# ESPROG.net
KiCad netlist of a schematic drawn in EAGLE
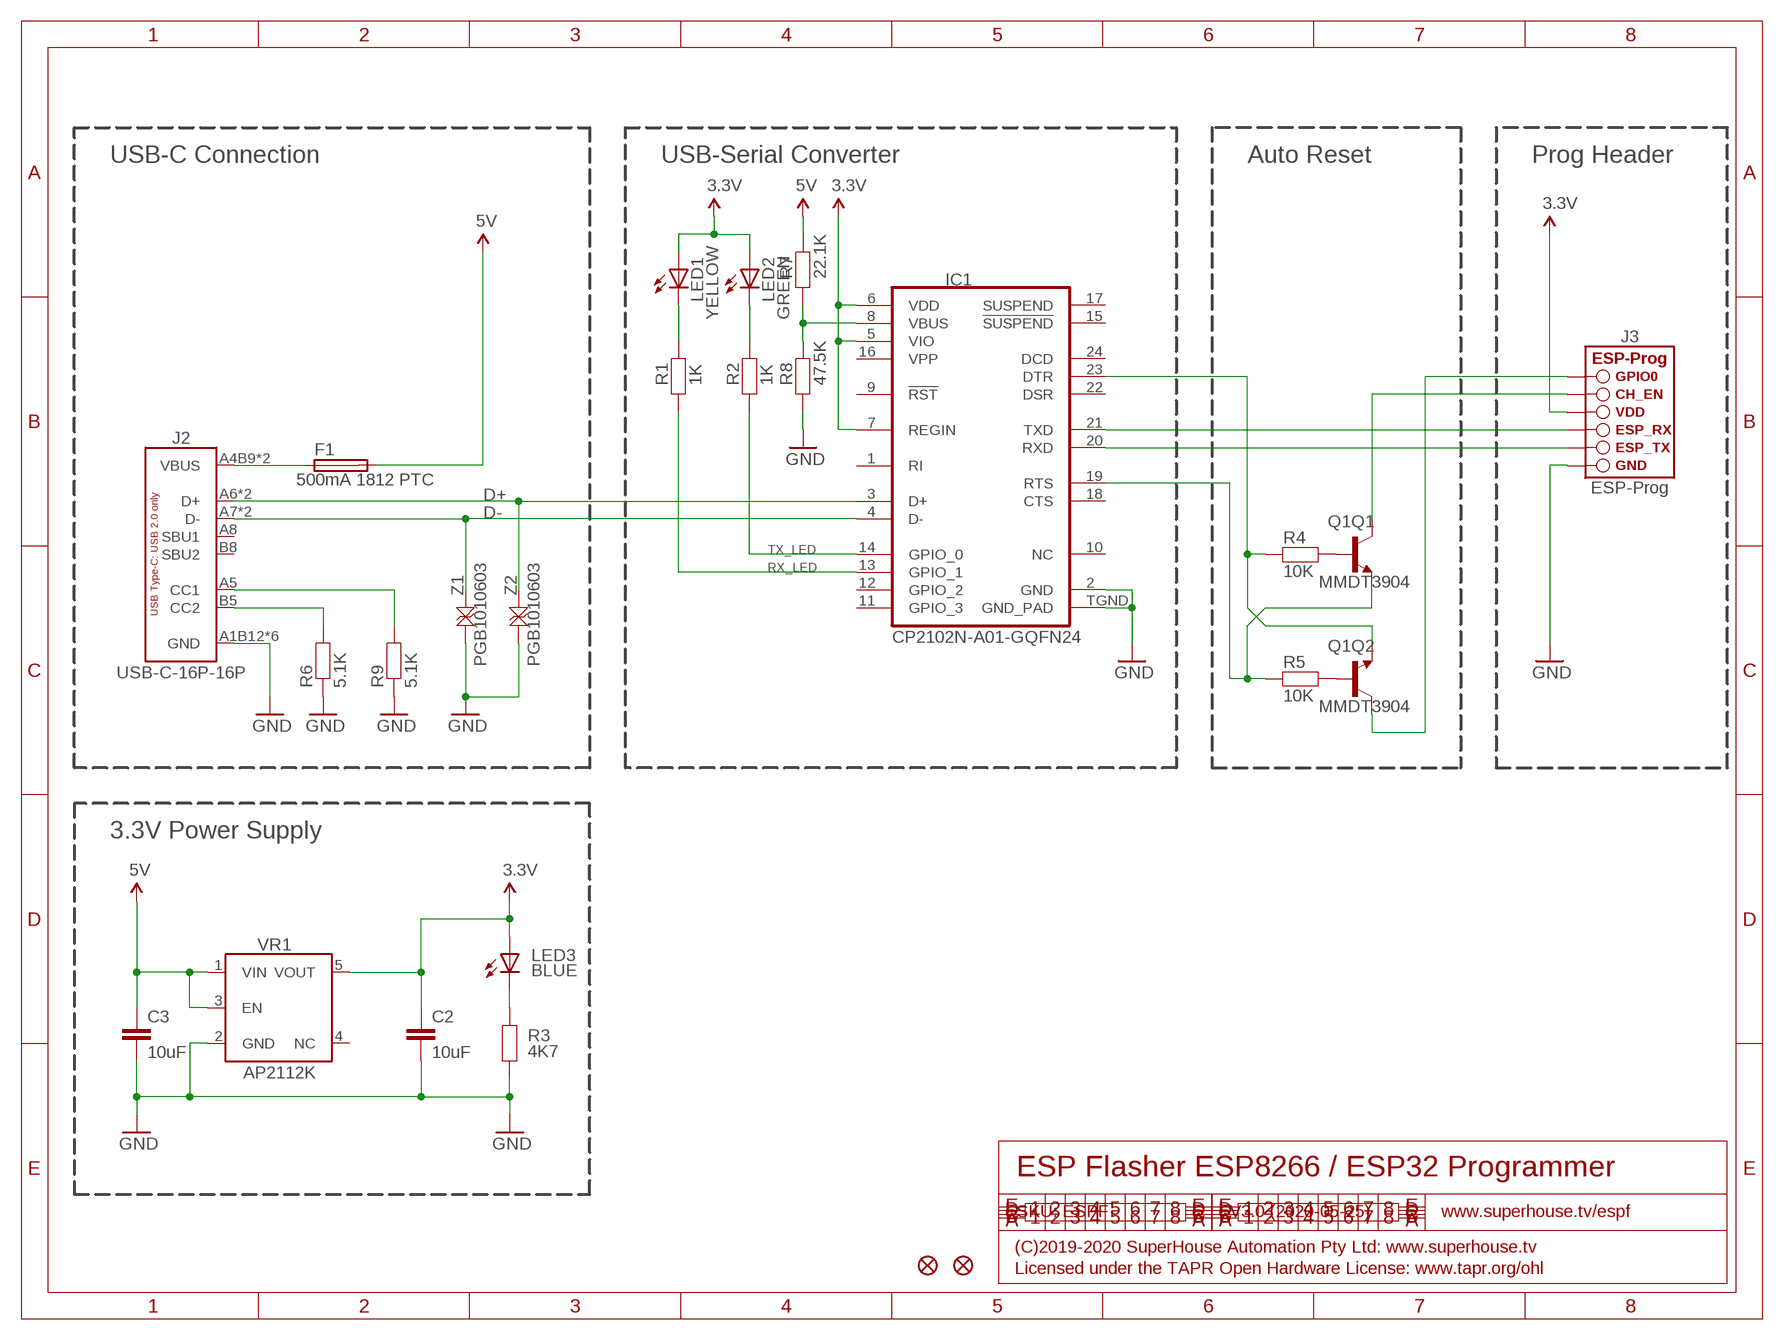
[diagram p0: schematic, sheet 1]

(export (version "E")
  (design (tool "Eeschema 10.0.6"))
  (components
    (comp (ref "C2")
      (value "10uF")
      (footprint "eagle-import:C0805")
      (libsource (lib "eagle-import") (part "CAP0805"))
    )
    (comp (ref "C3")
      (value "10uF")
      (footprint "eagle-import:C0805")
      (libsource (lib "eagle-import") (part "CAP0805"))
    )
    (comp (ref "F1")
      (value "500mA 1812 PTC")
      (footprint "eagle-import:1812")
      (libsource (lib "eagle-import") (part "PTC050"))
    )
    (comp (ref "FID1")
      (value "FIDUCIAL1X2.5")
      (footprint "eagle-import:FIDUCIAL-1X2.5")
      (libsource (lib "eagle-import") (part "FIDUCIAL1X2.5"))
    )
    (comp (ref "FID2")
      (value "FIDUCIAL1X2.5")
      (footprint "eagle-import:FIDUCIAL-1X2.5")
      (libsource (lib "eagle-import") (part "FIDUCIAL1X2.5"))
    )
    (comp (ref "IC1")
      (value "CP2102N-A01-GQFN24")
      (footprint "eagle-import:QFN-24")
      (libsource (lib "eagle-import") (part "CP2104"))
    )
    (comp (ref "J2")
      (value "USB-C-16P-16P")
      (footprint "eagle-import:USB-C-16P")
      (libsource (lib "eagle-import") (part "USB-C-16P-16P"))
    )
    (comp (ref "J3")
      (value "ESP-PROG-1X6-2.54-PINS-RA")
      (footprint "eagle-import:1X6-2.54-PINS-RA")
      (libsource (lib "eagle-import") (part "ESP-PROG-1X6-2.54-PINS-RA"))
    )
    (comp (ref "LED1")
      (value "YELLOW")
      (footprint "eagle-import:LED-0603")
      (libsource (lib "eagle-import") (part "LED0603"))
    )
    (comp (ref "LED2")
      (value "GREEN")
      (footprint "eagle-import:LED-0603")
      (libsource (lib "eagle-import") (part "LED0603"))
    )
    (comp (ref "LED3")
      (value "BLUE")
      (footprint "eagle-import:LED-0603")
      (libsource (lib "eagle-import") (part "LED0603"))
    )
    (comp (ref "Q1")
      (value "MMDT3904")
      (footprint "eagle-import:SOT-363")
      (libsource (lib "eagle-import") (part "TRANS_NPN_DUAL-MMDT3904"))
    )
    (comp (ref "R1")
      (value "1K")
      (footprint "eagle-import:R0603")
      (libsource (lib "eagle-import") (part "RESISTOR0603"))
    )
    (comp (ref "R2")
      (value "1K")
      (footprint "eagle-import:R0603")
      (libsource (lib "eagle-import") (part "RESISTOR0603"))
    )
    (comp (ref "R3")
      (value "4K7")
      (footprint "eagle-import:R0603")
      (libsource (lib "eagle-import") (part "RESISTOR0603"))
    )
    (comp (ref "R4")
      (value "10K")
      (footprint "eagle-import:R0603")
      (libsource (lib "eagle-import") (part "RESISTOR0603"))
    )
    (comp (ref "R5")
      (value "10K")
      (footprint "eagle-import:R0603")
      (libsource (lib "eagle-import") (part "RESISTOR0603"))
    )
    (comp (ref "R6")
      (value "5.1K")
      (footprint "eagle-import:R0603")
      (libsource (lib "eagle-import") (part "RESISTOR0603"))
    )
    (comp (ref "R7")
      (value "22.1K")
      (footprint "eagle-import:R0603")
      (libsource (lib "eagle-import") (part "RESISTOR0603"))
    )
    (comp (ref "R8")
      (value "47.5K")
      (footprint "eagle-import:R0603")
      (libsource (lib "eagle-import") (part "RESISTOR0603"))
    )
    (comp (ref "R9")
      (value "5.1K")
      (footprint "eagle-import:R0603")
      (libsource (lib "eagle-import") (part "RESISTOR0603"))
    )
    (comp (ref "VR1")
      (value "AP2112KSOT25")
      (footprint "eagle-import:SOT23-5")
      (libsource (lib "eagle-import") (part "AP2112KSOT25"))
    )
    (comp (ref "Z1")
      (value "PGB1010603")
      (footprint "eagle-import:TVS0603")
      (libsource (lib "eagle-import") (part "TVS0603"))
    )
    (comp (ref "Z2")
      (value "PGB1010603")
      (footprint "eagle-import:TVS0603")
      (libsource (lib "eagle-import") (part "TVS0603"))
    )
  )
  (nets
    (net (code "1") (name "/D+") (class "Default")
      (node (ref "IC1") (pin "3") (pinfunction "D+_3") (pintype "bidirectional"))
      (node (ref "J2") (pin "A6") (pinfunction "D+_A6") (pintype "bidirectional"))
      (node (ref "J2") (pin "B6") (pinfunction "D+_B6") (pintype "bidirectional"))
      (node (ref "Z2") (pin "2") (pinfunction "2_2") (pintype "passive"))
    )
    (net (code "2") (name "/D-") (class "Default")
      (node (ref "IC1") (pin "4") (pinfunction "D-_4") (pintype "bidirectional"))
      (node (ref "J2") (pin "A7") (pinfunction "D-_A7") (pintype "bidirectional"))
      (node (ref "J2") (pin "B7") (pinfunction "D-_B7") (pintype "bidirectional"))
      (node (ref "Z1") (pin "2") (pinfunction "2_2") (pintype "passive"))
    )
    (net (code "3") (name "/RX_LED") (class "Default")
      (node (ref "IC1") (pin "13") (pinfunction "GPIO_1_13") (pintype "bidirectional"))
      (node (ref "R1") (pin "1") (pinfunction "1_1") (pintype "passive"))
    )
    (net (code "4") (name "/TX_LED") (class "Default")
      (node (ref "IC1") (pin "14") (pinfunction "GPIO_0_14") (pintype "bidirectional"))
      (node (ref "R2") (pin "1") (pinfunction "1_1") (pintype "passive"))
    )
    (net (code "5") (name "3.3V") (class "Default")
      (node (ref "C2") (pin "1") (pinfunction "1_1") (pintype "passive"))
      (node (ref "IC1") (pin "5") (pinfunction "VIO_5") (pintype "bidirectional"))
      (node (ref "IC1") (pin "6") (pinfunction "VDD_6") (pintype "power_in"))
      (node (ref "IC1") (pin "7") (pinfunction "REGIN_7") (pintype "power_in"))
      (node (ref "J3") (pin "4") (pinfunction "VDD_4") (pintype "passive"))
      (node (ref "LED1") (pin "A") (pinfunction "A_A") (pintype "passive"))
      (node (ref "LED2") (pin "A") (pinfunction "A_A") (pintype "passive"))
      (node (ref "LED3") (pin "A") (pinfunction "A_A") (pintype "passive"))
      (node (ref "VR1") (pin "5") (pinfunction "VOUT_5") (pintype "bidirectional"))
    )
    (net (code "6") (name "5V") (class "Default")
      (node (ref "C3") (pin "1") (pinfunction "1_1") (pintype "passive"))
      (node (ref "F1") (pin "2") (pinfunction "2_2") (pintype "passive"))
      (node (ref "R7") (pin "2") (pinfunction "2_2") (pintype "passive"))
      (node (ref "VR1") (pin "1") (pinfunction "VIN_1") (pintype "bidirectional"))
      (node (ref "VR1") (pin "3") (pinfunction "EN_3") (pintype "bidirectional"))
    )
    (net (code "7") (name "GND") (class "Default")
      (node (ref "C2") (pin "2") (pinfunction "2_2") (pintype "passive"))
      (node (ref "C3") (pin "2") (pinfunction "2_2") (pintype "passive"))
      (node (ref "IC1") (pin "2") (pinfunction "GND_2") (pintype "power_in"))
      (node (ref "IC1") (pin "TGND") (pinfunction "GND_PAD_TGND") (pintype "power_in"))
      (node (ref "J2") (pin "A12B1") (pinfunction "GND_A12B1") (pintype "power_in"))
      (node (ref "J2") (pin "A1B12") (pinfunction "GND_A1B12") (pintype "power_in"))
      (node (ref "J2") (pin "FIX1") (pinfunction "GND_FIX1") (pintype "power_in"))
      (node (ref "J2") (pin "FIX2") (pinfunction "GND_FIX2") (pintype "power_in"))
      (node (ref "J2") (pin "FIX3") (pinfunction "GND_FIX3") (pintype "power_in"))
      (node (ref "J2") (pin "FIX4") (pinfunction "GND_FIX4") (pintype "power_in"))
      (node (ref "J3") (pin "1") (pinfunction "GND_1") (pintype "passive"))
      (node (ref "R3") (pin "1") (pinfunction "1_1") (pintype "passive"))
      (node (ref "R6") (pin "1") (pinfunction "1_1") (pintype "passive"))
      (node (ref "R8") (pin "1") (pinfunction "1_1") (pintype "passive"))
      (node (ref "R9") (pin "1") (pinfunction "1_1") (pintype "passive"))
      (node (ref "VR1") (pin "2") (pinfunction "GND_2") (pintype "bidirectional"))
      (node (ref "Z1") (pin "1") (pinfunction "1_1") (pintype "passive"))
      (node (ref "Z2") (pin "1") (pinfunction "1_1") (pintype "passive"))
    )
    (net (code "8") (name "Net-(F1-Pad1)") (class "Default")
      (node (ref "F1") (pin "1") (pinfunction "1_1") (pintype "passive"))
      (node (ref "J2") (pin "A4B9") (pinfunction "VBUS_A4B9") (pintype "power_in"))
      (node (ref "J2") (pin "A9B4") (pinfunction "VBUS_A9B4") (pintype "power_in"))
    )
    (net (code "9") (name "Net-(IC1-DTR)") (class "Default")
      (node (ref "IC1") (pin "23") (pinfunction "DTR_23") (pintype "output"))
      (node (ref "Q1") (pin "1") (pinfunction "E_1") (pintype "passive"))
      (node (ref "R4") (pin "1") (pinfunction "1_1") (pintype "passive"))
    )
    (net (code "10") (name "Net-(IC1-RTS)") (class "Default")
      (node (ref "IC1") (pin "19") (pinfunction "RTS_19") (pintype "output"))
      (node (ref "Q1") (pin "4") (pinfunction "E_4") (pintype "passive"))
      (node (ref "R5") (pin "1") (pinfunction "1_1") (pintype "passive"))
    )
    (net (code "11") (name "Net-(IC1-RXD)") (class "Default")
      (node (ref "IC1") (pin "20") (pinfunction "RXD_20") (pintype "input"))
      (node (ref "J3") (pin "2") (pinfunction "ESP_TX_2") (pintype "passive"))
    )
    (net (code "12") (name "Net-(IC1-TXD)") (class "Default")
      (node (ref "IC1") (pin "21") (pinfunction "TXD_21") (pintype "output"))
      (node (ref "J3") (pin "3") (pinfunction "ESP_RX_3") (pintype "passive"))
    )
    (net (code "13") (name "Net-(IC1-VBUS)") (class "Default")
      (node (ref "IC1") (pin "8") (pinfunction "VBUS_8") (pintype "bidirectional"))
      (node (ref "R7") (pin "1") (pinfunction "1_1") (pintype "passive"))
      (node (ref "R8") (pin "2") (pinfunction "2_2") (pintype "passive"))
    )
    (net (code "14") (name "Net-(J2-CC1)") (class "Default")
      (node (ref "J2") (pin "A5") (pinfunction "CC1_A5") (pintype "bidirectional"))
      (node (ref "R9") (pin "2") (pinfunction "2_2") (pintype "passive"))
    )
    (net (code "15") (name "Net-(J2-CC2)") (class "Default")
      (node (ref "J2") (pin "B5") (pinfunction "CC2_B5") (pintype "bidirectional"))
      (node (ref "R6") (pin "2") (pinfunction "2_2") (pintype "passive"))
    )
    (net (code "16") (name "Net-(J3-CH_EN)") (class "Default")
      (node (ref "J3") (pin "5") (pinfunction "CH_EN_5") (pintype "passive"))
      (node (ref "Q1") (pin "3") (pinfunction "C_3") (pintype "passive"))
    )
    (net (code "17") (name "Net-(J3-GPIO0)") (class "Default")
      (node (ref "J3") (pin "6") (pinfunction "GPIO0_6") (pintype "passive"))
      (node (ref "Q1") (pin "6") (pinfunction "C_6") (pintype "passive"))
    )
    (net (code "18") (name "Net-(LED1-PadC)") (class "Default")
      (node (ref "LED1") (pin "C") (pinfunction "C_C") (pintype "passive"))
      (node (ref "R1") (pin "2") (pinfunction "2_2") (pintype "passive"))
    )
    (net (code "19") (name "Net-(LED2-PadC)") (class "Default")
      (node (ref "LED2") (pin "C") (pinfunction "C_C") (pintype "passive"))
      (node (ref "R2") (pin "2") (pinfunction "2_2") (pintype "passive"))
    )
    (net (code "20") (name "Net-(LED3-PadC)") (class "Default")
      (node (ref "LED3") (pin "C") (pinfunction "C_C") (pintype "passive"))
      (node (ref "R3") (pin "2") (pinfunction "2_2") (pintype "passive"))
    )
    (net (code "21") (name "Net-(Q1A-B)") (class "Default")
      (node (ref "Q1") (pin "5") (pinfunction "B_5") (pintype "passive"))
      (node (ref "R4") (pin "2") (pinfunction "2_2") (pintype "passive"))
    )
    (net (code "22") (name "Net-(Q1B-B)") (class "Default")
      (node (ref "Q1") (pin "2") (pinfunction "B_2") (pintype "passive"))
      (node (ref "R5") (pin "2") (pinfunction "2_2") (pintype "passive"))
    )
    (net (code "23") (name "unconnected-(IC1-CTS-Pad18)") (class "Default")
      (node (ref "IC1") (pin "18") (pinfunction "CTS_18") (pintype "input"))
    )
    (net (code "24") (name "unconnected-(IC1-DCD-Pad24)") (class "Default")
      (node (ref "IC1") (pin "24") (pinfunction "DCD_24") (pintype "input"))
    )
    (net (code "25") (name "unconnected-(IC1-DSR-Pad22)") (class "Default")
      (node (ref "IC1") (pin "22") (pinfunction "DSR_22") (pintype "input"))
    )
    (net (code "26") (name "unconnected-(IC1-GPIO_2-Pad12)") (class "Default")
      (node (ref "IC1") (pin "12") (pinfunction "GPIO_2_12") (pintype "bidirectional"))
    )
    (net (code "27") (name "unconnected-(IC1-GPIO_3-Pad11)") (class "Default")
      (node (ref "IC1") (pin "11") (pinfunction "GPIO_3_11") (pintype "bidirectional"))
    )
    (net (code "28") (name "unconnected-(IC1-NC-Pad10)") (class "Default")
      (node (ref "IC1") (pin "10") (pinfunction "NC_10") (pintype "input"))
    )
    (net (code "29") (name "unconnected-(IC1-RI-Pad1)") (class "Default")
      (node (ref "IC1") (pin "1") (pinfunction "RI_1") (pintype "input"))
    )
    (net (code "30") (name "unconnected-(IC1-SUSPEND-Pad17)") (class "Default")
      (node (ref "IC1") (pin "17") (pinfunction "SUSPEND_17") (pintype "output"))
    )
    (net (code "31") (name "unconnected-(IC1-VPP-Pad16)") (class "Default")
      (node (ref "IC1") (pin "16") (pinfunction "VPP_16") (pintype "bidirectional"))
    )
    (net (code "32") (name "unconnected-(IC1-~{RST}-Pad9)") (class "Default")
      (node (ref "IC1") (pin "9") (pinfunction "~{RST}_9") (pintype "bidirectional"))
    )
    (net (code "33") (name "unconnected-(IC1-~{SUSPEND}-Pad15)") (class "Default")
      (node (ref "IC1") (pin "15") (pinfunction "~{SUSPEND}_15") (pintype "output"))
    )
    (net (code "34") (name "unconnected-(J2-SBU1-PadA8)") (class "Default")
      (node (ref "J2") (pin "A8") (pinfunction "SBU1_A8") (pintype "bidirectional"))
    )
    (net (code "35") (name "unconnected-(J2-SBU2-PadB8)") (class "Default")
      (node (ref "J2") (pin "B8") (pinfunction "SBU2_B8") (pintype "bidirectional"))
    )
    (net (code "36") (name "unconnected-(VR1-NC-Pad4)") (class "Default")
      (node (ref "VR1") (pin "4") (pinfunction "NC_4") (pintype "bidirectional"))
    )
  )
)
